# Blinker_04.net
KiCad netlist of a schematic drawn in EAGLE
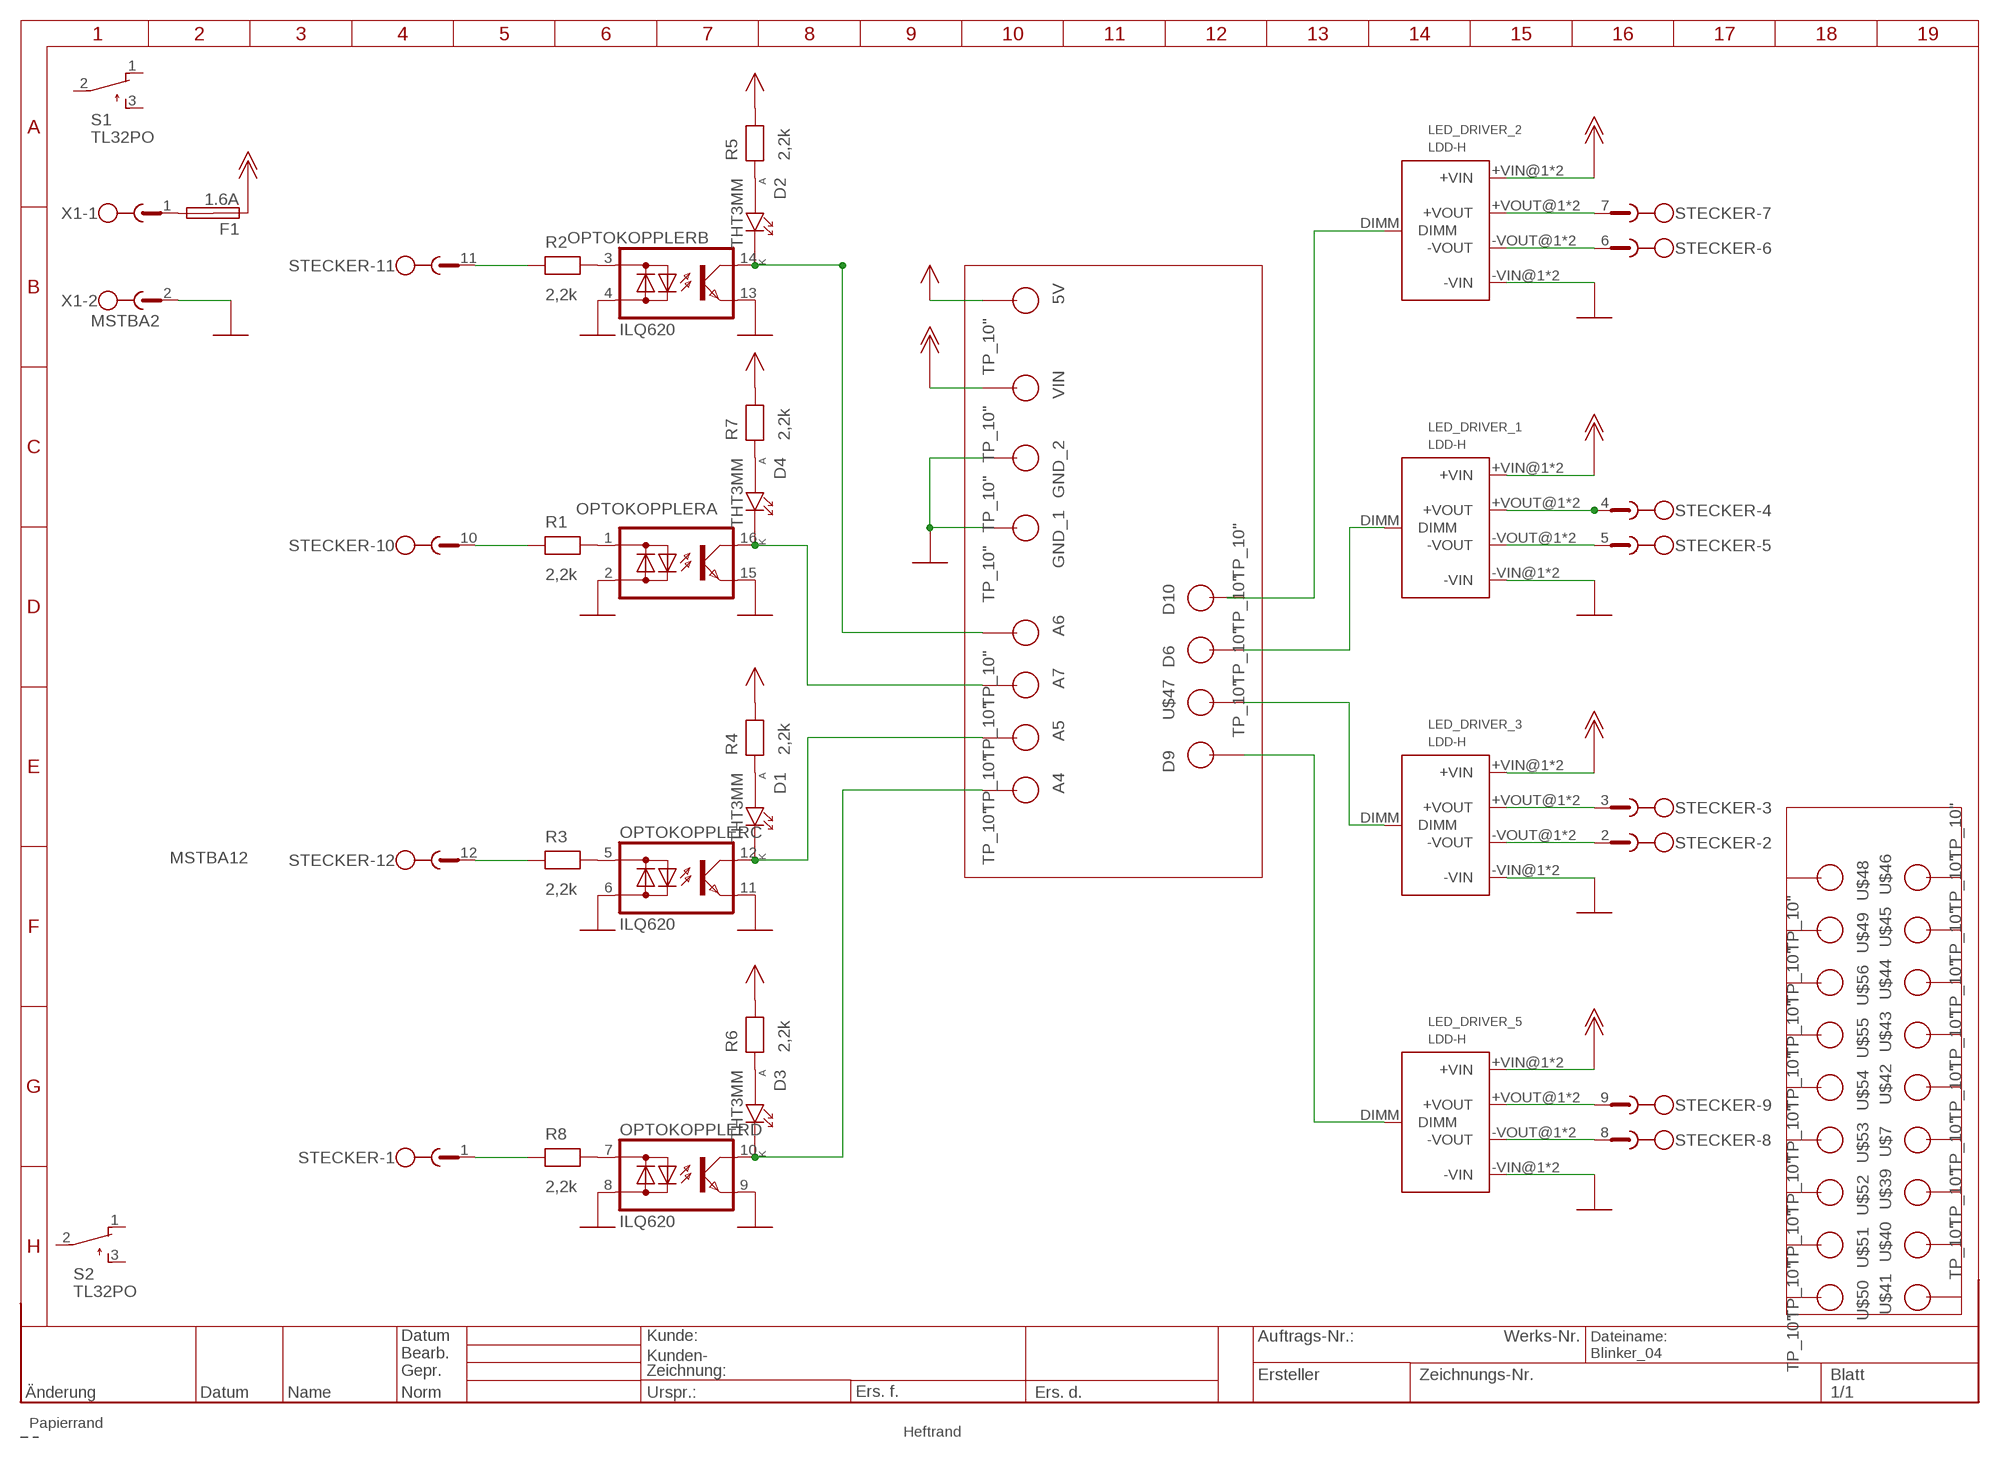
[diagram p0: schematic, sheet 1]

(export (version "E")
  (design (tool "Eeschema 10.0.6"))
  (components
    (comp (ref "5V")
      (value "TP_10\"")
      (footprint "eagle-import:TP_10")
      (libsource (lib "eagle-import") (part "TP_10{dblquote}"))
    )
    (comp (ref "A4")
      (value "TP_10\"")
      (footprint "eagle-import:TP_10")
      (libsource (lib "eagle-import") (part "TP_10{dblquote}"))
    )
    (comp (ref "A5")
      (value "TP_10\"")
      (footprint "eagle-import:TP_10")
      (libsource (lib "eagle-import") (part "TP_10{dblquote}"))
    )
    (comp (ref "A6")
      (value "TP_10\"")
      (footprint "eagle-import:TP_10")
      (libsource (lib "eagle-import") (part "TP_10{dblquote}"))
    )
    (comp (ref "A7")
      (value "TP_10\"")
      (footprint "eagle-import:TP_10")
      (libsource (lib "eagle-import") (part "TP_10{dblquote}"))
    )
    (comp (ref "D1")
      (value "THT3MM")
      (footprint "eagle-import:THT3MM")
      (libsource (lib "eagle-import") (part "THT3MM"))
    )
    (comp (ref "D2")
      (value "THT3MM")
      (footprint "eagle-import:THT3MM")
      (libsource (lib "eagle-import") (part "THT3MM"))
    )
    (comp (ref "D3")
      (value "THT3MM")
      (footprint "eagle-import:THT3MM")
      (libsource (lib "eagle-import") (part "THT3MM"))
    )
    (comp (ref "D4")
      (value "THT3MM")
      (footprint "eagle-import:THT3MM")
      (libsource (lib "eagle-import") (part "THT3MM"))
    )
    (comp (ref "D6")
      (value "TP_10\"")
      (footprint "eagle-import:TP_10")
      (libsource (lib "eagle-import") (part "TP_10{dblquote}"))
    )
    (comp (ref "D9")
      (value "TP_10\"")
      (footprint "eagle-import:TP_10")
      (libsource (lib "eagle-import") (part "TP_10{dblquote}"))
    )
    (comp (ref "D10")
      (value "TP_10\"")
      (footprint "eagle-import:TP_10")
      (libsource (lib "eagle-import") (part "TP_10{dblquote}"))
    )
    (comp (ref "F1")
      (value "1.6A")
      (footprint "eagle-import:SHK20Q")
      (libsource (lib "eagle-import") (part "SHK20Q"))
    )
    (comp (ref "GND_1")
      (value "TP_10\"")
      (footprint "eagle-import:TP_10")
      (libsource (lib "eagle-import") (part "TP_10{dblquote}"))
    )
    (comp (ref "GND_2")
      (value "TP_10\"")
      (footprint "eagle-import:TP_10")
      (libsource (lib "eagle-import") (part "TP_10{dblquote}"))
    )
    (comp (ref "LED_DRIVER_1")
      (value "LDD-H")
      (footprint "eagle-import:LDD-H")
      (libsource (lib "eagle-import") (part "LDD-H"))
    )
    (comp (ref "LED_DRIVER_2")
      (value "LDD-H")
      (footprint "eagle-import:LDD-H")
      (libsource (lib "eagle-import") (part "LDD-H"))
    )
    (comp (ref "LED_DRIVER_3")
      (value "LDD-H")
      (footprint "eagle-import:LDD-H")
      (libsource (lib "eagle-import") (part "LDD-H"))
    )
    (comp (ref "LED_DRIVER_5")
      (value "LDD-H")
      (footprint "eagle-import:LDD-H")
      (libsource (lib "eagle-import") (part "LDD-H"))
    )
    (comp (ref "OPTOKOPPLER")
      (value "ILQ620")
      (footprint "eagle-import:DIL16")
      (libsource (lib "eagle-import") (part "ILQ620"))
    )
    (comp (ref "R1")
      (value "2,2k")
      (footprint "eagle-import:R-10")
      (libsource (lib "eagle-import") (part "RESEU-10"))
    )
    (comp (ref "R2")
      (value "2,2k")
      (footprint "eagle-import:R-10")
      (libsource (lib "eagle-import") (part "RESEU-10"))
    )
    (comp (ref "R3")
      (value "2,2k")
      (footprint "eagle-import:R-10")
      (libsource (lib "eagle-import") (part "RESEU-10"))
    )
    (comp (ref "R4")
      (value "2,2k")
      (footprint "eagle-import:R-10")
      (libsource (lib "eagle-import") (part "RESEU-10"))
    )
    (comp (ref "R5")
      (value "2,2k")
      (footprint "eagle-import:R-10")
      (libsource (lib "eagle-import") (part "RESEU-10"))
    )
    (comp (ref "R6")
      (value "2,2k")
      (footprint "eagle-import:R-10")
      (libsource (lib "eagle-import") (part "RESEU-10"))
    )
    (comp (ref "R7")
      (value "2,2k")
      (footprint "eagle-import:R-10")
      (libsource (lib "eagle-import") (part "RESEU-10"))
    )
    (comp (ref "R8")
      (value "2,2k")
      (footprint "eagle-import:R-10")
      (libsource (lib "eagle-import") (part "RESEU-10"))
    )
    (comp (ref "S1")
      (value "TL32PO")
      (footprint "eagle-import:TL3XPO")
      (libsource (lib "eagle-import") (part "TL32PO"))
    )
    (comp (ref "S2")
      (value "TL32PO")
      (footprint "eagle-import:TL3XPO")
      (libsource (lib "eagle-import") (part "TL32PO"))
    )
    (comp (ref "STECKER")
      (value "MSTBA12")
      (footprint "eagle-import:MSTBA12")
      (fields (field (name "MPN") "1757349"))
      (libsource (lib "eagle-import") (part "MSTBA12"))
    )
    (comp (ref "U$7")
      (value "TP_10\"")
      (footprint "eagle-import:TP_10")
      (libsource (lib "eagle-import") (part "TP_10{dblquote}"))
    )
    (comp (ref "U$39")
      (value "TP_10\"")
      (footprint "eagle-import:TP_10")
      (libsource (lib "eagle-import") (part "TP_10{dblquote}"))
    )
    (comp (ref "U$40")
      (value "TP_10\"")
      (footprint "eagle-import:TP_10")
      (libsource (lib "eagle-import") (part "TP_10{dblquote}"))
    )
    (comp (ref "U$41")
      (value "TP_10\"")
      (footprint "eagle-import:TP_10")
      (libsource (lib "eagle-import") (part "TP_10{dblquote}"))
    )
    (comp (ref "U$42")
      (value "TP_10\"")
      (footprint "eagle-import:TP_10")
      (libsource (lib "eagle-import") (part "TP_10{dblquote}"))
    )
    (comp (ref "U$43")
      (value "TP_10\"")
      (footprint "eagle-import:TP_10")
      (libsource (lib "eagle-import") (part "TP_10{dblquote}"))
    )
    (comp (ref "U$44")
      (value "TP_10\"")
      (footprint "eagle-import:TP_10")
      (libsource (lib "eagle-import") (part "TP_10{dblquote}"))
    )
    (comp (ref "U$45")
      (value "TP_10\"")
      (footprint "eagle-import:TP_10")
      (libsource (lib "eagle-import") (part "TP_10{dblquote}"))
    )
    (comp (ref "U$46")
      (value "TP_10\"")
      (footprint "eagle-import:TP_10")
      (libsource (lib "eagle-import") (part "TP_10{dblquote}"))
    )
    (comp (ref "U$47")
      (value "TP_10\"")
      (footprint "eagle-import:TP_10")
      (libsource (lib "eagle-import") (part "TP_10{dblquote}"))
    )
    (comp (ref "U$48")
      (value "TP_10\"")
      (footprint "eagle-import:TP_10")
      (libsource (lib "eagle-import") (part "TP_10{dblquote}"))
    )
    (comp (ref "U$49")
      (value "TP_10\"")
      (footprint "eagle-import:TP_10")
      (libsource (lib "eagle-import") (part "TP_10{dblquote}"))
    )
    (comp (ref "U$50")
      (value "TP_10\"")
      (footprint "eagle-import:TP_10")
      (libsource (lib "eagle-import") (part "TP_10{dblquote}"))
    )
    (comp (ref "U$51")
      (value "TP_10\"")
      (footprint "eagle-import:TP_10")
      (libsource (lib "eagle-import") (part "TP_10{dblquote}"))
    )
    (comp (ref "U$52")
      (value "TP_10\"")
      (footprint "eagle-import:TP_10")
      (libsource (lib "eagle-import") (part "TP_10{dblquote}"))
    )
    (comp (ref "U$53")
      (value "TP_10\"")
      (footprint "eagle-import:TP_10")
      (libsource (lib "eagle-import") (part "TP_10{dblquote}"))
    )
    (comp (ref "U$54")
      (value "TP_10\"")
      (footprint "eagle-import:TP_10")
      (libsource (lib "eagle-import") (part "TP_10{dblquote}"))
    )
    (comp (ref "U$55")
      (value "TP_10\"")
      (footprint "eagle-import:TP_10")
      (libsource (lib "eagle-import") (part "TP_10{dblquote}"))
    )
    (comp (ref "U$56")
      (value "TP_10\"")
      (footprint "eagle-import:TP_10")
      (libsource (lib "eagle-import") (part "TP_10{dblquote}"))
    )
    (comp (ref "VIN")
      (value "TP_10\"")
      (footprint "eagle-import:TP_10")
      (libsource (lib "eagle-import") (part "TP_10{dblquote}"))
    )
    (comp (ref "X1")
      (value "MSTBA2")
      (footprint "eagle-import:MSTBA2")
      (fields (field (name "MF") "FARNELL") (field (name "MPN") "1757242"))
      (libsource (lib "eagle-import") (part "MSTBA2"))
    )
  )
  (nets
    (net (code "1") (name "+5V") (class "Default")
      (node (ref "5V") (pin "P$1") (pinfunction "TP_13_P$1") (pintype "bidirectional"))
      (node (ref "R4") (pin "2") (pinfunction "2_2") (pintype "passive"))
      (node (ref "R5") (pin "2") (pinfunction "2_2") (pintype "passive"))
      (node (ref "R6") (pin "2") (pinfunction "2_2") (pintype "passive"))
      (node (ref "R7") (pin "2") (pinfunction "2_2") (pintype "passive"))
    )
    (net (code "2") (name "+12V") (class "Default")
      (node (ref "F1") (pin "1A") (pinfunction "1A_1A") (pintype "passive"))
      (node (ref "LED_DRIVER_1") (pin "+VIN@1") (pinfunction "+VIN_+VIN@1") (pintype "power_in"))
      (node (ref "LED_DRIVER_1") (pin "+VIN@2") (pinfunction "+VIN_+VIN@2") (pintype "power_in"))
      (node (ref "LED_DRIVER_2") (pin "+VIN@1") (pinfunction "+VIN_+VIN@1") (pintype "power_in"))
      (node (ref "LED_DRIVER_2") (pin "+VIN@2") (pinfunction "+VIN_+VIN@2") (pintype "power_in"))
      (node (ref "LED_DRIVER_3") (pin "+VIN@1") (pinfunction "+VIN_+VIN@1") (pintype "power_in"))
      (node (ref "LED_DRIVER_3") (pin "+VIN@2") (pinfunction "+VIN_+VIN@2") (pintype "power_in"))
      (node (ref "LED_DRIVER_5") (pin "+VIN@1") (pinfunction "+VIN_+VIN@1") (pintype "power_in"))
      (node (ref "LED_DRIVER_5") (pin "+VIN@2") (pinfunction "+VIN_+VIN@2") (pintype "power_in"))
      (node (ref "VIN") (pin "P$1") (pinfunction "TP_13_P$1") (pintype "bidirectional"))
    )
    (net (code "3") (name "GND") (class "Default")
      (node (ref "GND_1") (pin "P$1") (pinfunction "TP_13_P$1") (pintype "bidirectional"))
      (node (ref "GND_2") (pin "P$1") (pinfunction "TP_13_P$1") (pintype "bidirectional"))
      (node (ref "LED_DRIVER_1") (pin "-VIN@1") (pinfunction "-VIN_-VIN@1") (pintype "power_in"))
      (node (ref "LED_DRIVER_1") (pin "-VIN@2") (pinfunction "-VIN_-VIN@2") (pintype "power_in"))
      (node (ref "LED_DRIVER_2") (pin "-VIN@1") (pinfunction "-VIN_-VIN@1") (pintype "power_in"))
      (node (ref "LED_DRIVER_2") (pin "-VIN@2") (pinfunction "-VIN_-VIN@2") (pintype "power_in"))
      (node (ref "LED_DRIVER_3") (pin "-VIN@1") (pinfunction "-VIN_-VIN@1") (pintype "power_in"))
      (node (ref "LED_DRIVER_3") (pin "-VIN@2") (pinfunction "-VIN_-VIN@2") (pintype "power_in"))
      (node (ref "LED_DRIVER_5") (pin "-VIN@1") (pinfunction "-VIN_-VIN@1") (pintype "power_in"))
      (node (ref "LED_DRIVER_5") (pin "-VIN@2") (pinfunction "-VIN_-VIN@2") (pintype "power_in"))
      (node (ref "OPTOKOPPLER") (pin "11") (pinfunction "E_11") (pintype "passive"))
      (node (ref "OPTOKOPPLER") (pin "13") (pinfunction "E_13") (pintype "passive"))
      (node (ref "OPTOKOPPLER") (pin "15") (pinfunction "E_15") (pintype "passive"))
      (node (ref "OPTOKOPPLER") (pin "2") (pinfunction "AC2_2") (pintype "passive"))
      (node (ref "OPTOKOPPLER") (pin "4") (pinfunction "AC2_4") (pintype "passive"))
      (node (ref "OPTOKOPPLER") (pin "6") (pinfunction "AC2_6") (pintype "passive"))
      (node (ref "OPTOKOPPLER") (pin "8") (pinfunction "AC2_8") (pintype "passive"))
      (node (ref "OPTOKOPPLER") (pin "9") (pinfunction "E_9") (pintype "passive"))
      (node (ref "X1") (pin "2") (pinfunction "1_2") (pintype "passive"))
    )
    (net (code "4") (name "Net-(A4-TP_13)") (class "Default")
      (node (ref "A4") (pin "P$1") (pinfunction "TP_13_P$1") (pintype "bidirectional"))
      (node (ref "D3") (pin "K") (pinfunction "P2K_K") (pintype "bidirectional"))
      (node (ref "OPTOKOPPLER") (pin "10") (pinfunction "C_10") (pintype "passive"))
    )
    (net (code "5") (name "Net-(A5-TP_13)") (class "Default")
      (node (ref "A5") (pin "P$1") (pinfunction "TP_13_P$1") (pintype "bidirectional"))
      (node (ref "D1") (pin "K") (pinfunction "P2K_K") (pintype "bidirectional"))
      (node (ref "OPTOKOPPLER") (pin "12") (pinfunction "C_12") (pintype "passive"))
    )
    (net (code "6") (name "Net-(A6-TP_13)") (class "Default")
      (node (ref "A6") (pin "P$1") (pinfunction "TP_13_P$1") (pintype "bidirectional"))
      (node (ref "D2") (pin "K") (pinfunction "P2K_K") (pintype "bidirectional"))
      (node (ref "OPTOKOPPLER") (pin "14") (pinfunction "C_14") (pintype "passive"))
    )
    (net (code "7") (name "Net-(A7-TP_13)") (class "Default")
      (node (ref "A7") (pin "P$1") (pinfunction "TP_13_P$1") (pintype "bidirectional"))
      (node (ref "D4") (pin "K") (pinfunction "P2K_K") (pintype "bidirectional"))
      (node (ref "OPTOKOPPLER") (pin "16") (pinfunction "C_16") (pintype "passive"))
    )
    (net (code "8") (name "Net-(D1-P1A)") (class "Default")
      (node (ref "D1") (pin "A") (pinfunction "P1A_A") (pintype "bidirectional"))
      (node (ref "R4") (pin "1") (pinfunction "1_1") (pintype "passive"))
    )
    (net (code "9") (name "Net-(D2-P1A)") (class "Default")
      (node (ref "D2") (pin "A") (pinfunction "P1A_A") (pintype "bidirectional"))
      (node (ref "R5") (pin "1") (pinfunction "1_1") (pintype "passive"))
    )
    (net (code "10") (name "Net-(D3-P1A)") (class "Default")
      (node (ref "D3") (pin "A") (pinfunction "P1A_A") (pintype "bidirectional"))
      (node (ref "R6") (pin "1") (pinfunction "1_1") (pintype "passive"))
    )
    (net (code "11") (name "Net-(D4-P1A)") (class "Default")
      (node (ref "D4") (pin "A") (pinfunction "P1A_A") (pintype "bidirectional"))
      (node (ref "R7") (pin "1") (pinfunction "1_1") (pintype "passive"))
    )
    (net (code "12") (name "Net-(D6-TP_13)") (class "Default")
      (node (ref "D6") (pin "P$1") (pinfunction "TP_13_P$1") (pintype "bidirectional"))
      (node (ref "LED_DRIVER_1") (pin "DIMM") (pinfunction "DIMM_DIMM") (pintype "input"))
    )
    (net (code "13") (name "Net-(D9-TP_13)") (class "Default")
      (node (ref "D9") (pin "P$1") (pinfunction "TP_13_P$1") (pintype "bidirectional"))
      (node (ref "LED_DRIVER_5") (pin "DIMM") (pinfunction "DIMM_DIMM") (pintype "input"))
    )
    (net (code "14") (name "Net-(F1-Pad2A)") (class "Default")
      (node (ref "F1") (pin "2A") (pinfunction "2A_2A") (pintype "passive"))
      (node (ref "X1") (pin "1") (pinfunction "1_1") (pintype "passive"))
    )
    (net (code "15") (name "Net-(OPTOKOPPLERA-AC1)") (class "Default")
      (node (ref "OPTOKOPPLER") (pin "1") (pinfunction "AC1_1") (pintype "passive"))
      (node (ref "R1") (pin "2") (pinfunction "2_2") (pintype "passive"))
    )
    (net (code "16") (name "Net-(OPTOKOPPLERB-AC1)") (class "Default")
      (node (ref "OPTOKOPPLER") (pin "3") (pinfunction "AC1_3") (pintype "passive"))
      (node (ref "R2") (pin "2") (pinfunction "2_2") (pintype "passive"))
    )
    (net (code "17") (name "Net-(OPTOKOPPLERC-AC1)") (class "Default")
      (node (ref "OPTOKOPPLER") (pin "5") (pinfunction "AC1_5") (pintype "passive"))
      (node (ref "R3") (pin "2") (pinfunction "2_2") (pintype "passive"))
    )
    (net (code "18") (name "Net-(OPTOKOPPLERD-AC1)") (class "Default")
      (node (ref "OPTOKOPPLER") (pin "7") (pinfunction "AC1_7") (pintype "passive"))
      (node (ref "R8") (pin "2") (pinfunction "2_2") (pintype "passive"))
    )
    (net (code "19") (name "Net-(R8-Pad1)") (class "Default")
      (node (ref "R8") (pin "1") (pinfunction "1_1") (pintype "passive"))
      (node (ref "STECKER") (pin "1") (pinfunction "1_1") (pintype "passive"))
    )
    (net (code "20") (name "Net-(STECKERB-1)") (class "Default")
      (node (ref "R1") (pin "1") (pinfunction "1_1") (pintype "passive"))
      (node (ref "STECKER") (pin "10") (pinfunction "1_10") (pintype "passive"))
    )
    (net (code "21") (name "Net-(STECKERC-1)") (class "Default")
      (node (ref "R2") (pin "1") (pinfunction "1_1") (pintype "passive"))
      (node (ref "STECKER") (pin "11") (pinfunction "1_11") (pintype "passive"))
    )
    (net (code "22") (name "Net-(STECKERD-1)") (class "Default")
      (node (ref "R3") (pin "1") (pinfunction "1_1") (pintype "passive"))
      (node (ref "STECKER") (pin "12") (pinfunction "1_12") (pintype "passive"))
    )
    (net (code "23") (name "Net-(STECKERE-1)") (class "Default")
      (node (ref "LED_DRIVER_3") (pin "-VOUT@1") (pinfunction "-VOUT_-VOUT@1") (pintype "output"))
      (node (ref "LED_DRIVER_3") (pin "-VOUT@2") (pinfunction "-VOUT_-VOUT@2") (pintype "output"))
      (node (ref "STECKER") (pin "2") (pinfunction "1_2") (pintype "passive"))
    )
    (net (code "24") (name "Net-(STECKERF-1)") (class "Default")
      (node (ref "LED_DRIVER_3") (pin "+VOUT@1") (pinfunction "+VOUT_+VOUT@1") (pintype "output"))
      (node (ref "LED_DRIVER_3") (pin "+VOUT@2") (pinfunction "+VOUT_+VOUT@2") (pintype "output"))
      (node (ref "STECKER") (pin "3") (pinfunction "1_3") (pintype "passive"))
    )
    (net (code "25") (name "Net-(STECKERG-1)") (class "Default")
      (node (ref "LED_DRIVER_1") (pin "+VOUT@1") (pinfunction "+VOUT_+VOUT@1") (pintype "output"))
      (node (ref "LED_DRIVER_1") (pin "+VOUT@2") (pinfunction "+VOUT_+VOUT@2") (pintype "output"))
      (node (ref "STECKER") (pin "4") (pinfunction "1_4") (pintype "passive"))
    )
    (net (code "26") (name "Net-(STECKERH-1)") (class "Default")
      (node (ref "LED_DRIVER_1") (pin "-VOUT@1") (pinfunction "-VOUT_-VOUT@1") (pintype "output"))
      (node (ref "LED_DRIVER_1") (pin "-VOUT@2") (pinfunction "-VOUT_-VOUT@2") (pintype "output"))
      (node (ref "STECKER") (pin "5") (pinfunction "1_5") (pintype "passive"))
    )
    (net (code "27") (name "Net-(STECKERI-1)") (class "Default")
      (node (ref "LED_DRIVER_2") (pin "-VOUT@1") (pinfunction "-VOUT_-VOUT@1") (pintype "output"))
      (node (ref "LED_DRIVER_2") (pin "-VOUT@2") (pinfunction "-VOUT_-VOUT@2") (pintype "output"))
      (node (ref "STECKER") (pin "6") (pinfunction "1_6") (pintype "passive"))
    )
    (net (code "28") (name "Net-(STECKERJ-1)") (class "Default")
      (node (ref "LED_DRIVER_2") (pin "+VOUT@1") (pinfunction "+VOUT_+VOUT@1") (pintype "output"))
      (node (ref "LED_DRIVER_2") (pin "+VOUT@2") (pinfunction "+VOUT_+VOUT@2") (pintype "output"))
      (node (ref "STECKER") (pin "7") (pinfunction "1_7") (pintype "passive"))
    )
    (net (code "29") (name "Net-(STECKERK-1)") (class "Default")
      (node (ref "LED_DRIVER_5") (pin "-VOUT@1") (pinfunction "-VOUT_-VOUT@1") (pintype "output"))
      (node (ref "LED_DRIVER_5") (pin "-VOUT@2") (pinfunction "-VOUT_-VOUT@2") (pintype "output"))
      (node (ref "STECKER") (pin "8") (pinfunction "1_8") (pintype "passive"))
    )
    (net (code "30") (name "Net-(STECKERL-1)") (class "Default")
      (node (ref "LED_DRIVER_5") (pin "+VOUT@1") (pinfunction "+VOUT_+VOUT@1") (pintype "output"))
      (node (ref "LED_DRIVER_5") (pin "+VOUT@2") (pinfunction "+VOUT_+VOUT@2") (pintype "output"))
      (node (ref "STECKER") (pin "9") (pinfunction "1_9") (pintype "passive"))
    )
    (net (code "31") (name "Net-(U$47-TP_13)") (class "Default")
      (node (ref "LED_DRIVER_3") (pin "DIMM") (pinfunction "DIMM_DIMM") (pintype "input"))
      (node (ref "U$47") (pin "P$1") (pinfunction "TP_13_P$1") (pintype "bidirectional"))
    )
    (net (code "32") (name "unconnected-(D10-TP_13-PadP$1)") (class "Default")
      (node (ref "D10") (pin "P$1") (pinfunction "TP_13_P$1") (pintype "bidirectional"))
    )
    (net (code "33") (name "unconnected-(F1-Pad1B)") (class "Default")
      (node (ref "F1") (pin "1B") (pinfunction "1B_1B") (pintype "passive"))
    )
    (net (code "34") (name "unconnected-(F1-Pad2B)") (class "Default")
      (node (ref "F1") (pin "2B") (pinfunction "2B_2B") (pintype "passive"))
    )
    (net (code "35") (name "unconnected-(LED_DRIVER_2-PadDIMM)") (class "Default")
      (node (ref "LED_DRIVER_2") (pin "DIMM") (pinfunction "DIMM_DIMM") (pintype "input"))
    )
    (net (code "36") (name "unconnected-(S1-O-Pad1)") (class "Default")
      (node (ref "S1") (pin "1") (pinfunction "O_1") (pintype "passive"))
    )
    (net (code "37") (name "unconnected-(S1-P-Pad2)") (class "Default")
      (node (ref "S1") (pin "2") (pinfunction "P_2") (pintype "passive"))
    )
    (net (code "38") (name "unconnected-(S1-S-Pad3)") (class "Default")
      (node (ref "S1") (pin "3") (pinfunction "S_3") (pintype "passive"))
    )
    (net (code "39") (name "unconnected-(S2-O-Pad1)") (class "Default")
      (node (ref "S2") (pin "1") (pinfunction "O_1") (pintype "passive"))
    )
    (net (code "40") (name "unconnected-(S2-P-Pad2)") (class "Default")
      (node (ref "S2") (pin "2") (pinfunction "P_2") (pintype "passive"))
    )
    (net (code "41") (name "unconnected-(S2-S-Pad3)") (class "Default")
      (node (ref "S2") (pin "3") (pinfunction "S_3") (pintype "passive"))
    )
    (net (code "42") (name "unconnected-(U$7-TP_13-PadP$1)") (class "Default")
      (node (ref "U$7") (pin "P$1") (pinfunction "TP_13_P$1") (pintype "bidirectional"))
    )
    (net (code "43") (name "unconnected-(U$39-TP_13-PadP$1)") (class "Default")
      (node (ref "U$39") (pin "P$1") (pinfunction "TP_13_P$1") (pintype "bidirectional"))
    )
    (net (code "44") (name "unconnected-(U$40-TP_13-PadP$1)") (class "Default")
      (node (ref "U$40") (pin "P$1") (pinfunction "TP_13_P$1") (pintype "bidirectional"))
    )
    (net (code "45") (name "unconnected-(U$41-TP_13-PadP$1)") (class "Default")
      (node (ref "U$41") (pin "P$1") (pinfunction "TP_13_P$1") (pintype "bidirectional"))
    )
    (net (code "46") (name "unconnected-(U$42-TP_13-PadP$1)") (class "Default")
      (node (ref "U$42") (pin "P$1") (pinfunction "TP_13_P$1") (pintype "bidirectional"))
    )
    (net (code "47") (name "unconnected-(U$43-TP_13-PadP$1)") (class "Default")
      (node (ref "U$43") (pin "P$1") (pinfunction "TP_13_P$1") (pintype "bidirectional"))
    )
    (net (code "48") (name "unconnected-(U$44-TP_13-PadP$1)") (class "Default")
      (node (ref "U$44") (pin "P$1") (pinfunction "TP_13_P$1") (pintype "bidirectional"))
    )
    (net (code "49") (name "unconnected-(U$45-TP_13-PadP$1)") (class "Default")
      (node (ref "U$45") (pin "P$1") (pinfunction "TP_13_P$1") (pintype "bidirectional"))
    )
    (net (code "50") (name "unconnected-(U$46-TP_13-PadP$1)") (class "Default")
      (node (ref "U$46") (pin "P$1") (pinfunction "TP_13_P$1") (pintype "bidirectional"))
    )
    (net (code "51") (name "unconnected-(U$48-TP_13-PadP$1)") (class "Default")
      (node (ref "U$48") (pin "P$1") (pinfunction "TP_13_P$1") (pintype "bidirectional"))
    )
    (net (code "52") (name "unconnected-(U$49-TP_13-PadP$1)") (class "Default")
      (node (ref "U$49") (pin "P$1") (pinfunction "TP_13_P$1") (pintype "bidirectional"))
    )
    (net (code "53") (name "unconnected-(U$50-TP_13-PadP$1)") (class "Default")
      (node (ref "U$50") (pin "P$1") (pinfunction "TP_13_P$1") (pintype "bidirectional"))
    )
    (net (code "54") (name "unconnected-(U$51-TP_13-PadP$1)") (class "Default")
      (node (ref "U$51") (pin "P$1") (pinfunction "TP_13_P$1") (pintype "bidirectional"))
    )
    (net (code "55") (name "unconnected-(U$52-TP_13-PadP$1)") (class "Default")
      (node (ref "U$52") (pin "P$1") (pinfunction "TP_13_P$1") (pintype "bidirectional"))
    )
    (net (code "56") (name "unconnected-(U$53-TP_13-PadP$1)") (class "Default")
      (node (ref "U$53") (pin "P$1") (pinfunction "TP_13_P$1") (pintype "bidirectional"))
    )
    (net (code "57") (name "unconnected-(U$54-TP_13-PadP$1)") (class "Default")
      (node (ref "U$54") (pin "P$1") (pinfunction "TP_13_P$1") (pintype "bidirectional"))
    )
    (net (code "58") (name "unconnected-(U$55-TP_13-PadP$1)") (class "Default")
      (node (ref "U$55") (pin "P$1") (pinfunction "TP_13_P$1") (pintype "bidirectional"))
    )
    (net (code "59") (name "unconnected-(U$56-TP_13-PadP$1)") (class "Default")
      (node (ref "U$56") (pin "P$1") (pinfunction "TP_13_P$1") (pintype "bidirectional"))
    )
  )
)
